# Carte_TryOhm.net
KiCad netlist of a schematic drawn in Altium Designer
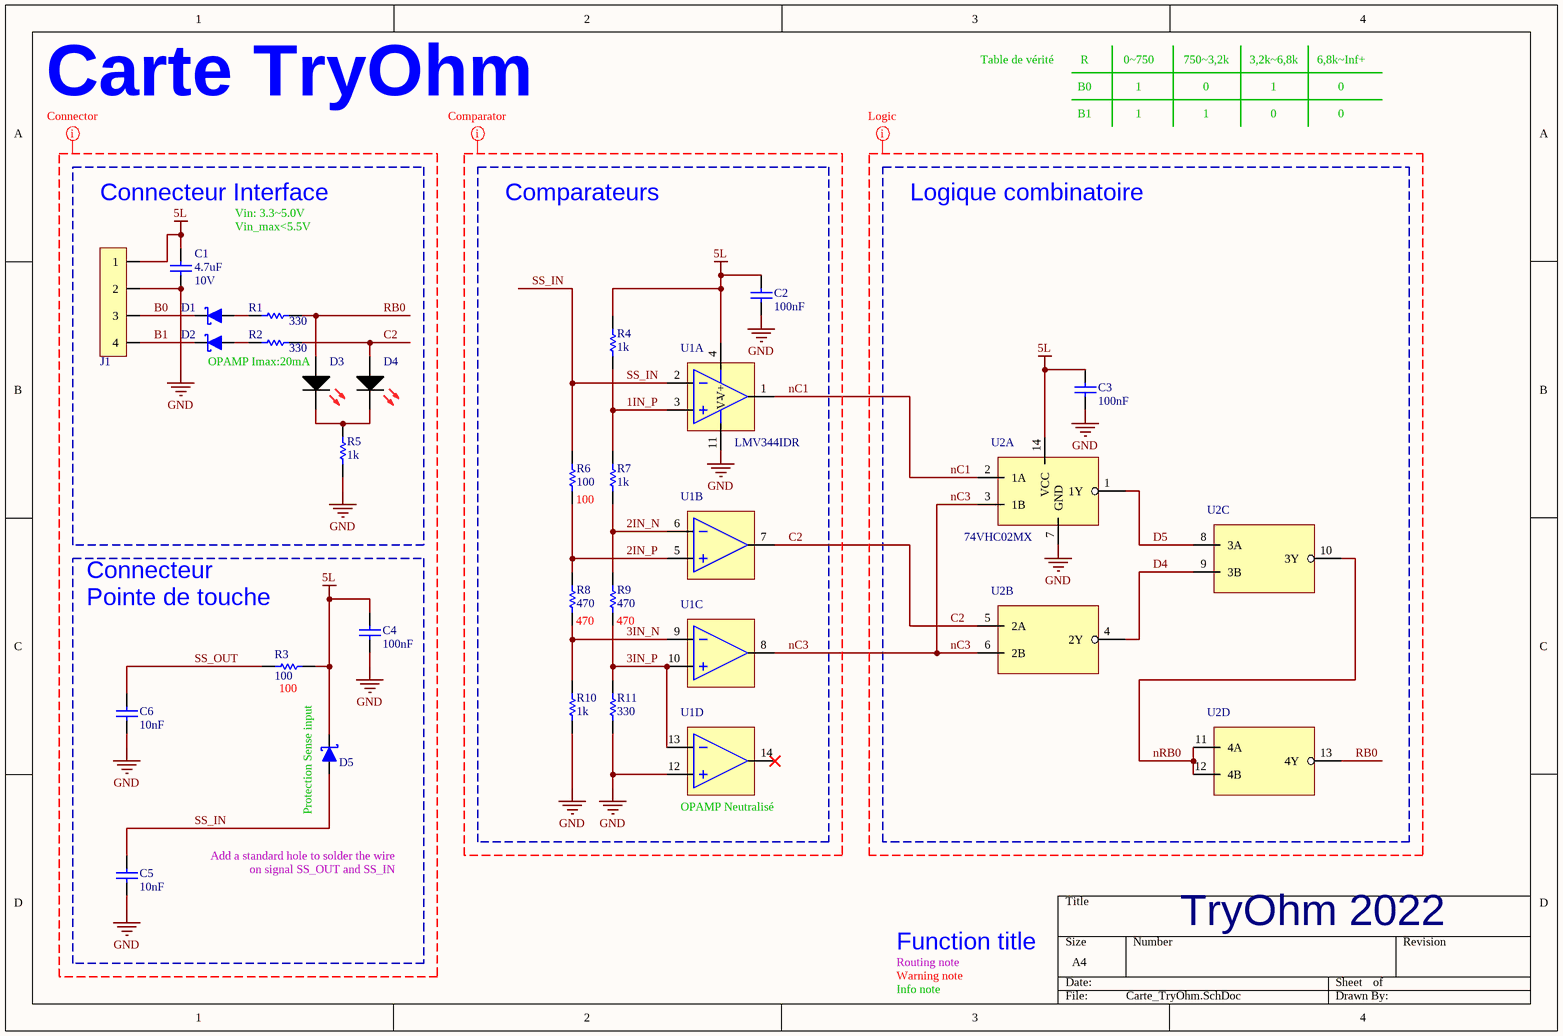
[diagram p0: Carte_TryOhm.SchDoc]

(export (version "E")
  (design (tool "Eeschema 10.0.6"))
  (components
    (comp (ref "C1")
      (value "4.7uF")
      (footprint "WCAP-CSGP_0603, 1.6x0.8x0.8")
      (description "CAP CER 4.7UF 10V X5R 0603")
      (fields
        (field (name "MANUFACTURER") "Wurth Elektronik")
        (field (name "MANUFACTURER PART NUMBER") "885012106012")
        (field (name "RATEDVOLTAGE") "10V")
      )
      (libsource (lib "Condensateur") (part "WCAP-CSGP, 885012106012"))
    )
    (comp (ref "C2")
      (value "100nF")
      (footprint "WCAP-CSGP_0603, 1.6x0.8x0.8")
      (description "CAP CER 100nF 50V X7R 0603")
      (fields
        (field (name "MANUFACTURER") "Wurth Elektronik")
        (field (name "MANUFACTURER PART NUMBER") "885012206095")
      )
      (libsource (lib "Condensateur") (part "WCAP-CSGP, 885012206095"))
    )
    (comp (ref "C3")
      (value "100nF")
      (footprint "WCAP-CSGP_0603, 1.6x0.8x0.8")
      (description "CAP CER 100nF 50V X7R 0603")
      (fields
        (field (name "MANUFACTURER") "Wurth Elektronik")
        (field (name "MANUFACTURER PART NUMBER") "885012206095")
      )
      (libsource (lib "Condensateur") (part "WCAP-CSGP, 885012206095"))
    )
    (comp (ref "C4")
      (value "100nF")
      (footprint "WCAP-CSGP_0603, 1.6x0.8x0.8")
      (description "CAP CER 100nF 50V X7R 0603")
      (fields
        (field (name "MANUFACTURER") "Wurth Elektronik")
        (field (name "MANUFACTURER PART NUMBER") "885012206095")
      )
      (libsource (lib "Condensateur") (part "WCAP-CSGP, 885012206095"))
    )
    (comp (ref "C5")
      (value "10nF")
      (footprint "WCAP-CSGP_0603, 1.6x0.8x0.8")
      (description "CAP CER 10nF 50V X7R 0603")
      (fields
        (field (name "MANUFACTURER") "Wurth Elektronik")
        (field (name "MANUFACTURER PART NUMBER") "885012206089")
      )
      (libsource (lib "Condensateur") (part "WCAP-CSGP, 885012206089"))
    )
    (comp (ref "C6")
      (value "10nF")
      (footprint "WCAP-CSGP_0603, 1.6x0.8x0.8")
      (description "CAP CER 10nF 50V X7R 0603")
      (fields
        (field (name "MANUFACTURER") "Wurth Elektronik")
        (field (name "MANUFACTURER PART NUMBER") "885012206089")
      )
      (libsource (lib "Condensateur") (part "WCAP-CSGP, 885012206089"))
    )
    (comp (ref "D1")
      (value "RBR3MM40ATFTR")
      (footprint "SOD-123FL")
      (description "DIODE SCHOTTKY 40V 3A SOD123-FL")
      (fields (field (name "MANUFACTURER") "ROHM"))
      (libsource (lib "Diode") (part "RBR3MM40ATFTR"))
    )
    (comp (ref "D2")
      (value "RBR3MM40ATFTR")
      (footprint "SOD-123FL")
      (description "DIODE SCHOTTKY 40V 3A SOD123-FL")
      (fields (field (name "MANUFACTURER") "ROHM"))
      (libsource (lib "Diode") (part "RBR3MM40ATFTR"))
    )
    (comp (ref "D3")
      (value "150060RS75000")
      (footprint "SMCW_0603")
      (description "SMD mono-color Chip LED, WL-SMCW, Red")
      (fields (field (name "MANUFACTURER") "Wurth Elektronik"))
      (libsource (lib "Opto") (part "WL-SMCW 0603  150060RS75000"))
    )
    (comp (ref "D4")
      (value "150060RS75000")
      (footprint "SMCW_0603")
      (description "SMD mono-color Chip LED, WL-SMCW, Red")
      (fields (field (name "MANUFACTURER") "Wurth Elektronik"))
      (libsource (lib "Opto") (part "WL-SMCW 0603  150060RS75000"))
    )
    (comp (ref "D5")
      (value "RBR3MM40ATFTR")
      (footprint "SOD-123FL")
      (description "DIODE SCHOTTKY 40V 3A SOD123-FL")
      (fields (field (name "MANUFACTURER") "ROHM"))
      (libsource (lib "Diode") (part "RBR3MM40ATFTR"))
    )
    (comp (ref "J1")
      (value "22-03-2041")
      (footprint "22-03-2041")
      (description "CONN HEADER VERT 4POS 2.54MM")
      (fields (field (name "MANUFACTURER") "MOLEX"))
      (libsource (lib "Connecteurs") (part "22-03-2041"))
    )
    (comp (ref "R1")
      (value "330")
      (footprint "RESC1608X06N")
      (description "RES SMD 330 OHM 1% 1/10W 0603")
      (fields
        (field (name "MANUFACTURER") "Yageo")
        (field (name "MANUFACTURER PART NUMBER") "RC0603FR-07330RL")
      )
      (libsource (lib "Resistance") (part "RC0603FR-07330RL"))
    )
    (comp (ref "R2")
      (value "330")
      (footprint "RESC1608X06N")
      (description "RES SMD 330 OHM 1% 1/10W 0603")
      (fields
        (field (name "MANUFACTURER") "Yageo")
        (field (name "MANUFACTURER PART NUMBER") "RC0603FR-07330RL")
      )
      (libsource (lib "Resistance") (part "RC0603FR-07330RL"))
    )
    (comp (ref "R3")
      (value "100")
      (footprint "RESC1608X06N")
      (description "RES SMD 330 OHM 1% 1/10W 0603")
      (fields
        (field (name "MANUFACTURER") "Yageo")
        (field (name "MANUFACTURER PART NUMBER") "RC0603FR-07100RL")
      )
      (libsource (lib "Resistance") (part "RC0603FR-07330RL"))
    )
    (comp (ref "R4")
      (value "1k")
      (footprint "RESC1608X06N")
      (description "RES SMD 1K OHM 1% 1/10W 0603")
      (fields
        (field (name "MANUFACTURER") "Yageo")
        (field (name "MANUFACTURER PART NUMBER") "RC0603FR-071KL")
      )
      (libsource (lib "Resistance") (part "RC0603FR-071KL"))
    )
    (comp (ref "R5")
      (value "1k")
      (footprint "RESC1608X06N")
      (description "RES SMD 1K OHM 1% 1/10W 0603")
      (fields
        (field (name "MANUFACTURER") "Yageo")
        (field (name "MANUFACTURER PART NUMBER") "RC0603FR-071KL")
      )
      (libsource (lib "Resistance") (part "RC0603FR-071KL"))
    )
    (comp (ref "R6")
      (value "100")
      (footprint "RESC1608X06N")
      (description "RES SMD 330 OHM 1% 1/10W 0603")
      (fields
        (field (name "MANUFACTURER") "Yageo")
        (field (name "MANUFACTURER PART NUMBER") "RC0603FR-07100RL")
      )
      (libsource (lib "Resistance") (part "RC0603FR-07330RL"))
    )
    (comp (ref "R7")
      (value "1k")
      (footprint "RESC1608X06N")
      (description "RES SMD 1K OHM 1% 1/10W 0603")
      (fields
        (field (name "MANUFACTURER") "Yageo")
        (field (name "MANUFACTURER PART NUMBER") "RC0603FR-071KL")
      )
      (libsource (lib "Resistance") (part "RC0603FR-071KL"))
    )
    (comp (ref "R8")
      (value "470")
      (footprint "RESC1608X06N")
      (description "RES SMD 330 OHM 1% 1/10W 0603")
      (fields
        (field (name "MANUFACTURER") "Yageo")
        (field (name "MANUFACTURER PART NUMBER") "RC0603FR-07470RL")
      )
      (libsource (lib "Resistance") (part "RC0603FR-07330RL"))
    )
    (comp (ref "R9")
      (value "470")
      (footprint "RESC1608X06N")
      (description "RES SMD 330 OHM 1% 1/10W 0603")
      (fields
        (field (name "MANUFACTURER") "Yageo")
        (field (name "MANUFACTURER PART NUMBER") "RC0603FR-07470RL")
      )
      (libsource (lib "Resistance") (part "RC0603FR-07330RL"))
    )
    (comp (ref "R10")
      (value "1k")
      (footprint "RESC1608X06N")
      (description "RES SMD 1K OHM 1% 1/10W 0603")
      (fields
        (field (name "MANUFACTURER") "Yageo")
        (field (name "MANUFACTURER PART NUMBER") "RC0603FR-071KL")
      )
      (libsource (lib "Resistance") (part "RC0603FR-071KL"))
    )
    (comp (ref "R11")
      (value "330")
      (footprint "RESC1608X06N")
      (description "RES SMD 330 OHM 1% 1/10W 0603")
      (fields
        (field (name "MANUFACTURER") "Yageo")
        (field (name "MANUFACTURER PART NUMBER") "RC0603FR-07330RL")
      )
      (libsource (lib "Resistance") (part "RC0603FR-07330RL"))
    )
    (comp (ref "U1")
      (value "LMV344IDR")
      (footprint "SOIC127P600X175-14N")
      (description "IC OPAMP GP 4 CIRCUIT 14SOIC")
      (fields (field (name "MANUFACTURER") "TEXAS INSTRUMENTS"))
      (libsource (lib "CI") (part "LMV344IDR"))
    )
    (comp (ref "U2")
      (value "74VHC02MX")
      (footprint "SOIC127P600X175-14N")
      (description "IC GATE NOR 4CH 2-INP 14SOIC")
      (fields (field (name "MANUFACTURER") "ONSEMI"))
      (libsource (lib "CI") (part "74VHC02MX"))
    )
  )
  (nets
    (net (code "1") (name "/1IN_P") (class "Default")
      (node (ref "R4") (pin "2") (pinfunction "2_2") (pintype "passive"))
      (node (ref "R7") (pin "1") (pinfunction "1_1") (pintype "passive"))
      (node (ref "U1") (pin "3") (pinfunction "1IN+_3") (pintype "passive"))
    )
    (net (code "2") (name "/2IN_N") (class "Default")
      (node (ref "R7") (pin "2") (pinfunction "2_2") (pintype "passive"))
      (node (ref "R9") (pin "1") (pinfunction "1_1") (pintype "passive"))
      (node (ref "U1") (pin "6") (pinfunction "2IN-_6") (pintype "passive"))
    )
    (net (code "3") (name "/2IN_P") (class "Default")
      (node (ref "R6") (pin "2") (pinfunction "2_2") (pintype "passive"))
      (node (ref "R8") (pin "1") (pinfunction "1_1") (pintype "passive"))
      (node (ref "U1") (pin "5") (pinfunction "2IN+_5") (pintype "passive"))
    )
    (net (code "4") (name "/3IN_N") (class "Default")
      (node (ref "R10") (pin "1") (pinfunction "1_1") (pintype "passive"))
      (node (ref "R8") (pin "2") (pinfunction "2_2") (pintype "passive"))
      (node (ref "U1") (pin "9") (pinfunction "3IN-_9") (pintype "passive"))
    )
    (net (code "5") (name "/3IN_P") (class "Default")
      (node (ref "R11") (pin "1") (pinfunction "1_1") (pintype "passive"))
      (node (ref "R9") (pin "2") (pinfunction "2_2") (pintype "passive"))
      (node (ref "U1") (pin "10") (pinfunction "3IN+_10") (pintype "passive"))
      (node (ref "U1") (pin "13") (pinfunction "4IN-_13") (pintype "passive"))
    )
    (net (code "6") (name "/B0") (class "Default")
      (node (ref "D1") (pin "2") (pintype "passive"))
      (node (ref "J1") (pin "3") (pinfunction "3_3") (pintype "passive"))
    )
    (net (code "7") (name "/B1") (class "Default")
      (node (ref "D2") (pin "2") (pintype "passive"))
      (node (ref "J1") (pin "4") (pinfunction "4_4") (pintype "passive"))
    )
    (net (code "8") (name "/C2") (class "Default")
      (node (ref "D4") (pin "2") (pinfunction "A_2") (pintype "passive"))
      (node (ref "R2") (pin "1") (pinfunction "1_1") (pintype "passive"))
      (node (ref "U1") (pin "7") (pinfunction "2OUT_7") (pintype "passive"))
      (node (ref "U2") (pin "5") (pinfunction "2A_5") (pintype "passive"))
    )
    (net (code "9") (name "/D4") (class "Default")
      (node (ref "U2") (pin "4") (pinfunction "2Y_4") (pintype "passive"))
      (node (ref "U2") (pin "9") (pinfunction "3B_9") (pintype "passive"))
    )
    (net (code "10") (name "/D5") (class "Default")
      (node (ref "U2") (pin "1") (pinfunction "1Y_1") (pintype "passive"))
      (node (ref "U2") (pin "8") (pinfunction "3A_8") (pintype "passive"))
    )
    (net (code "11") (name "/RB0") (class "Default")
      (node (ref "D3") (pin "2") (pinfunction "A_2") (pintype "passive"))
      (node (ref "R1") (pin "1") (pinfunction "1_1") (pintype "passive"))
      (node (ref "U2") (pin "13") (pinfunction "4Y_13") (pintype "passive"))
    )
    (net (code "12") (name "/SS_IN") (class "Default")
      (node (ref "C5") (pin "2") (pinfunction "2_2") (pintype "passive"))
      (node (ref "D5") (pin "1") (pintype "passive"))
      (node (ref "R6") (pin "1") (pinfunction "1_1") (pintype "passive"))
      (node (ref "U1") (pin "2") (pinfunction "1IN-_2") (pintype "passive"))
    )
    (net (code "13") (name "/SS_OUT") (class "Default")
      (node (ref "C6") (pin "2") (pinfunction "2_2") (pintype "passive"))
      (node (ref "R3") (pin "2") (pinfunction "2_2") (pintype "passive"))
    )
    (net (code "14") (name "/nC1") (class "Default")
      (node (ref "U1") (pin "1") (pinfunction "1OUT_1") (pintype "passive"))
      (node (ref "U2") (pin "2") (pinfunction "1A_2") (pintype "passive"))
    )
    (net (code "15") (name "/nC3") (class "Default")
      (node (ref "U1") (pin "8") (pinfunction "3OUT_8") (pintype "passive"))
      (node (ref "U2") (pin "3") (pinfunction "1B_3") (pintype "passive"))
      (node (ref "U2") (pin "6") (pinfunction "2B_6") (pintype "passive"))
    )
    (net (code "16") (name "/nRB0") (class "Default")
      (node (ref "U2") (pin "10") (pinfunction "3Y_10") (pintype "passive"))
      (node (ref "U2") (pin "11") (pinfunction "4A_11") (pintype "passive"))
      (node (ref "U2") (pin "12") (pinfunction "4B_12") (pintype "passive"))
    )
    (net (code "17") (name "5L") (class "Default")
      (node (ref "C1") (pin "1") (pinfunction "1_1") (pintype "passive"))
      (node (ref "C2") (pin "1") (pinfunction "1_1") (pintype "passive"))
      (node (ref "C3") (pin "1") (pinfunction "1_1") (pintype "passive"))
      (node (ref "C4") (pin "1") (pinfunction "1_1") (pintype "passive"))
      (node (ref "D5") (pin "2") (pintype "passive"))
      (node (ref "J1") (pin "1") (pinfunction "1_1") (pintype "passive"))
      (node (ref "R3") (pin "1") (pinfunction "1_1") (pintype "passive"))
      (node (ref "R4") (pin "1") (pinfunction "1_1") (pintype "passive"))
      (node (ref "U1") (pin "4") (pinfunction "V+_4") (pintype "passive"))
      (node (ref "U2") (pin "14") (pinfunction "VCC_14") (pintype "passive"))
    )
    (net (code "18") (name "GND") (class "Default")
      (node (ref "C1") (pin "2") (pinfunction "2_2") (pintype "passive"))
      (node (ref "C2") (pin "2") (pinfunction "2_2") (pintype "passive"))
      (node (ref "C3") (pin "2") (pinfunction "2_2") (pintype "passive"))
      (node (ref "C4") (pin "2") (pinfunction "2_2") (pintype "passive"))
      (node (ref "C5") (pin "1") (pinfunction "1_1") (pintype "passive"))
      (node (ref "C6") (pin "1") (pinfunction "1_1") (pintype "passive"))
      (node (ref "J1") (pin "2") (pinfunction "2_2") (pintype "passive"))
      (node (ref "R10") (pin "2") (pinfunction "2_2") (pintype "passive"))
      (node (ref "R11") (pin "2") (pinfunction "2_2") (pintype "passive"))
      (node (ref "R5") (pin "1") (pinfunction "1_1") (pintype "passive"))
      (node (ref "U1") (pin "11") (pinfunction "V-_11") (pintype "passive"))
      (node (ref "U1") (pin "12") (pinfunction "4IN+_12") (pintype "passive"))
      (node (ref "U2") (pin "7") (pinfunction "GND_7") (pintype "passive"))
    )
    (net (code "19") (name "Net-(D1-Pad1)") (class "Default")
      (node (ref "D1") (pin "1") (pintype "passive"))
      (node (ref "R1") (pin "2") (pinfunction "2_2") (pintype "passive"))
    )
    (net (code "20") (name "Net-(D2-Pad1)") (class "Default")
      (node (ref "D2") (pin "1") (pintype "passive"))
      (node (ref "R2") (pin "2") (pinfunction "2_2") (pintype "passive"))
    )
    (net (code "21") (name "Net-(D3-C)") (class "Default")
      (node (ref "D3") (pin "1") (pinfunction "C_1") (pintype "passive"))
      (node (ref "D4") (pin "1") (pinfunction "C_1") (pintype "passive"))
      (node (ref "R5") (pin "2") (pinfunction "2_2") (pintype "passive"))
    )
    (net (code "22") (name "unconnected-(U1D-4OUT-Pad14)") (class "Default")
      (node (ref "U1") (pin "14") (pinfunction "4OUT_14") (pintype "passive+no_connect"))
    )
  )
)
